# v3.net
KiCad netlist of a schematic drawn in Altium Designer
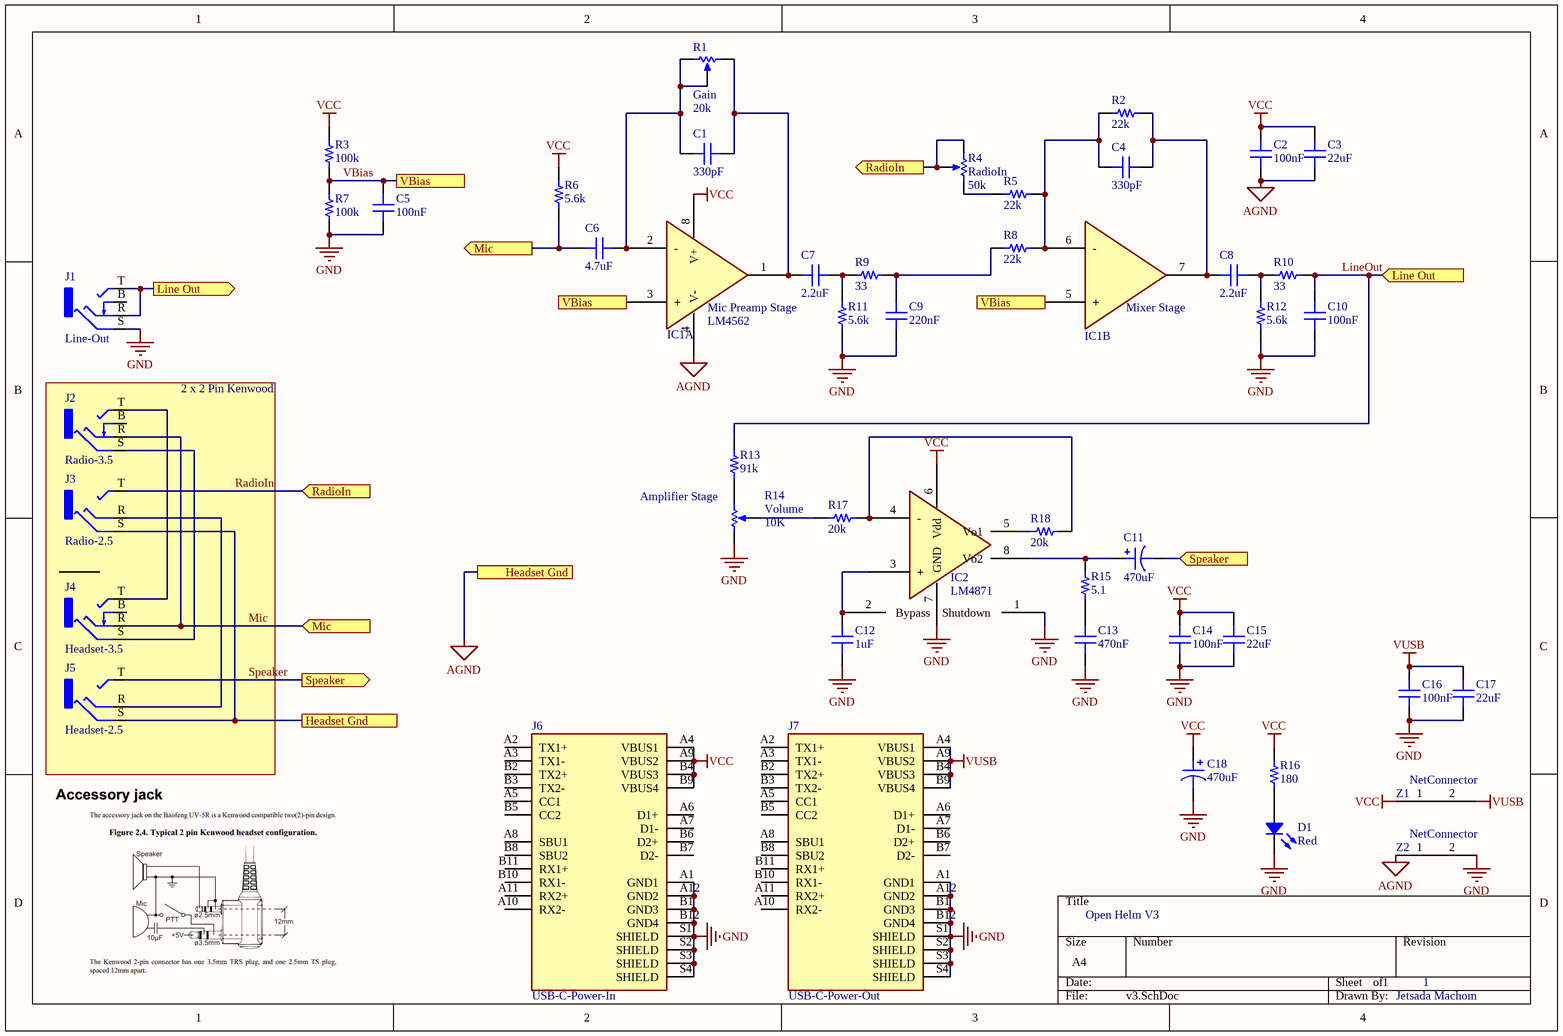
[diagram p0: v3.SchDoc]

(export (version "E")
  (design (tool "Eeschema 10.0.6"))
  (components
    (comp (ref "C1")
      (value "330pF")
      (footprint "CAP 0805_2012")
      (description "Multilayer Ceramic Capacitors MLCC - SMD/SMT 330pF 50V 0805 RoHS")
      (libsource (lib "Celestial Altium Library - altium_library") (part "Capacitor"))
    )
    (comp (ref "C2")
      (value "100nF")
      (footprint "CAP 0805_2012")
      (description "Multilayer Ceramic Capacitors MLCC - SMD/SMT 100nF 50V 0805 RoHS")
      (libsource (lib "Celestial Altium Library - altium_library") (part "Capacitor"))
    )
    (comp (ref "C3")
      (value "22uF")
      (footprint "CAP 0805_2012")
      (description "Multilayer Ceramic Capacitors MLCC - SMD/SMT 22uF 25V 0805 RoHS")
      (libsource (lib "Celestial Altium Library - altium_library") (part "Capacitor"))
    )
    (comp (ref "C4")
      (value "330pF")
      (footprint "CAP 0805_2012")
      (description "Multilayer Ceramic Capacitors MLCC - SMD/SMT 330pF 50V 0805 RoHS")
      (libsource (lib "Celestial Altium Library - altium_library") (part "Capacitor"))
    )
    (comp (ref "C5")
      (value "100nF")
      (footprint "CAP 0805_2012")
      (description "Multilayer Ceramic Capacitors MLCC - SMD/SMT 100nF 50V 0805 RoHS")
      (libsource (lib "Celestial Altium Library - altium_library") (part "Capacitor"))
    )
    (comp (ref "C6")
      (value "4.7uF")
      (footprint "CAP 0805_2012")
      (description "Multilayer Ceramic Capacitors MLCC - SMD/SMT 4.7uF 25V 0805 RoHS")
      (libsource (lib "Celestial Altium Library - altium_library") (part "Capacitor"))
    )
    (comp (ref "C7")
      (value "2.2uF")
      (footprint "CAP 0805_2012")
      (description "Multilayer Ceramic Capacitors MLCC - SMD/SMT 2.2uF 50V 0805 RoHS")
      (libsource (lib "Celestial Altium Library - altium_library") (part "Capacitor"))
    )
    (comp (ref "C8")
      (value "2.2uF")
      (footprint "CAP 0805_2012")
      (description "Multilayer Ceramic Capacitors MLCC - SMD/SMT 2.2uF 50V 0805 RoHS")
      (libsource (lib "Celestial Altium Library - altium_library") (part "Capacitor"))
    )
    (comp (ref "C9")
      (value "220nF")
      (footprint "CAP 0805_2012")
      (description "Multilayer Ceramic Capacitors MLCC - SMD/SMT 220nF 50V 0805 RoHS")
      (libsource (lib "Celestial Altium Library - altium_library") (part "Capacitor"))
    )
    (comp (ref "C10")
      (value "100nF")
      (footprint "CAP 0805_2012")
      (description "Multilayer Ceramic Capacitors MLCC - SMD/SMT 100nF 50V 0805 RoHS")
      (libsource (lib "Celestial Altium Library - altium_library") (part "Capacitor"))
    )
    (comp (ref "C11")
      (value "470uF")
      (footprint "EEEFT-D8")
      (description "SMD Aluminium Electrolytic Capacitor, Radial Can - SMD, 470 µF, 6.3 V, 0.16 ohm, FT Series")
      (libsource (lib "Celestial Altium Library - altium_library") (part "Polarised Capacitor"))
    )
    (comp (ref "C12")
      (value "1uF")
      (footprint "CAP 0805_2012")
      (description "Multilayer Ceramic Capacitors MLCC - SMD/SMT 100nF 50V 0805 RoHS")
      (libsource (lib "Celestial Altium Library - altium_library") (part "Capacitor"))
    )
    (comp (ref "C13")
      (value "470nF")
      (footprint "CAP 0805_2012")
      (description "Multilayer Ceramic Capacitors MLCC - SMD/SMT 470nF 50V 0805 RoHS")
      (libsource (lib "Celestial Altium Library - altium_library") (part "Capacitor"))
    )
    (comp (ref "C14")
      (value "100nF")
      (footprint "CAP 0805_2012")
      (description "Multilayer Ceramic Capacitors MLCC - SMD/SMT 100nF 50V 0805 RoHS")
      (libsource (lib "Celestial Altium Library - altium_library") (part "Capacitor"))
    )
    (comp (ref "C15")
      (value "22uF")
      (footprint "CAP 0805_2012")
      (description "Multilayer Ceramic Capacitors MLCC - SMD/SMT 22uF 25V 0805 RoHS")
      (libsource (lib "Celestial Altium Library - altium_library") (part "Capacitor"))
    )
    (comp (ref "C16")
      (value "100nF")
      (footprint "CAP 0805_2012")
      (description "Multilayer Ceramic Capacitors MLCC - SMD/SMT 100nF 50V 0805 RoHS")
      (libsource (lib "Celestial Altium Library - altium_library") (part "Capacitor"))
    )
    (comp (ref "C17")
      (value "22uF")
      (footprint "CAP 0805_2012")
      (description "Multilayer Ceramic Capacitors MLCC - SMD/SMT 22uF 25V 0805 RoHS")
      (libsource (lib "Celestial Altium Library - altium_library") (part "Capacitor"))
    )
    (comp (ref "C18")
      (value "470uF")
      (footprint "EEEFT-D8")
      (description "SMD Aluminium Electrolytic Capacitor, Radial Can - SMD, 470 µF, 10 V, 0.16 ohm, FT Series")
      (libsource (lib "") (part "Polarised Capacitor_1"))
    )
    (comp (ref "D1")
      (value "Red")
      (footprint "LED 0805_2012 RED")
      (description "LIGHT EMITTING DIODES (LED) RED 615~630NM 67~195MCD@20MA TOP VIEW 0805 ROHS")
      (libsource (lib "Celestial Altium Library - altium_library") (part "LED"))
    )
    (comp (ref "IC1")
      (value "LM4562")
      (footprint "LM4562")
      (description "Audio Power Amplifier, 2 Channel, ± 2.5V to ± 17V, SOIC, 8 Pins")
      (libsource (lib "ZLib") (part "LM4562"))
    )
    (comp (ref "IC2")
      (value "LM4871")
      (footprint "LM4871")
      (description "Audio Power Amplifier, 3 W, AB, 1 Channel, 2V to 5.5V, SOIC, 8 Pins")
      (libsource (lib "ZLib") (part "LM4871"))
    )
    (comp (ref "J1")
      (value "Line-Out")
      (footprint "KLBR4")
      (description "Phone Audio Connector, 3 Contacts, Socket, 3.5 mm, PCB Mount, Silver Plated Contacts, Metal Body")
      (libsource (lib "KLBR4") (part "KLBR4"))
    )
    (comp (ref "J2")
      (value "Radio-3.5")
      (footprint "KLBR4")
      (description "Phone Audio Connector, 3 Contacts, Socket, 3.5 mm, PCB Mount, Silver Plated Contacts, Metal Body")
      (libsource (lib "KLBR4") (part "KLBR4"))
    )
    (comp (ref "J3")
      (value "Radio-2.5")
      (footprint "LUMBERG150105")
      (description "Phone Audio Connector, 3 Contacts, Socket, 2.5 mm, PCB Mount, Silver Plated Contacts, Metal Body")
      (libsource (lib "ZLib") (part "LUMBERG150105"))
    )
    (comp (ref "J4")
      (value "Headset-3.5")
      (footprint "KLBR4")
      (description "Phone Audio Connector, 3 Contacts, Socket, 3.5 mm, PCB Mount, Silver Plated Contacts, Metal Body")
      (libsource (lib "KLBR4") (part "KLBR4"))
    )
    (comp (ref "J5")
      (value "Headset-2.5")
      (footprint "LUMBERG150105")
      (description "Phone Audio Connector, 3 Contacts, Socket, 2.5 mm, PCB Mount, Silver Plated Contacts, Metal Body")
      (libsource (lib "ZLib") (part "LUMBERG150105"))
    )
    (comp (ref "J6")
      (value "USB-C-Power-In")
      (footprint "MC001002")
      (description "USB Connector, USB Type C, USB 3.1, Receptacle, 24 Ways, Surface Mount, Through Hole Mount")
      (libsource (lib "ZLib") (part "USBC"))
    )
    (comp (ref "J7")
      (value "USB-C-Power-Out")
      (footprint "MC001002")
      (description "USB Connector, USB Type C, USB 3.1, Receptacle, 24 Ways, Surface Mount, Through Hole Mount")
      (libsource (lib "ZLib") (part "USBC"))
    )
    (comp (ref "R1")
      (value "Gain")
      (footprint "3224W")
      (description "20K ±10% ±100ppm/°C Variable Resistors")
      (fields (field (name "ALTIUM_VALUE") "20k"))
      (libsource (lib "ZLib") (part "RPot"))
    )
    (comp (ref "R2")
      (value "22k")
      (footprint "RES 0805_2012")
      (description "Chip Resistor - Surface Mount 22KOhms ±1% 1/8W 0805 RoHS")
      (libsource (lib "Celestial Altium Library - altium_library") (part "Resistor"))
    )
    (comp (ref "R3")
      (value "100k")
      (footprint "RES 0805_2012")
      (description "Chip Resistor - Surface Mount 100KOhms ±1% 1/8W 0805 RoHS")
      (libsource (lib "Celestial Altium Library - altium_library") (part "Resistor"))
    )
    (comp (ref "R4")
      (value "RadioIn")
      (footprint "3224W")
      (description "50K ±10% ±100ppm/°C Variable Resistors")
      (fields (field (name "ALTIUM_VALUE") "50k"))
      (libsource (lib "ZLib") (part "RPot"))
    )
    (comp (ref "R5")
      (value "22k")
      (footprint "RES 0805_2012")
      (description "Chip Resistor - Surface Mount 22KOhms ±1% 1/8W 0805 RoHS")
      (libsource (lib "Celestial Altium Library - altium_library") (part "Resistor"))
    )
    (comp (ref "R6")
      (value "5.6k")
      (footprint "RES 0805_2012")
      (description "Chip Resistor - Surface Mount 5.6KOhms ±1% 1/8W 0805 RoHS")
      (libsource (lib "Celestial Altium Library - altium_library") (part "Resistor"))
    )
    (comp (ref "R7")
      (value "100k")
      (footprint "RES 0805_2012")
      (description "Chip Resistor - Surface Mount 100KOhms ±1% 1/8W 0805 RoHS")
      (libsource (lib "Celestial Altium Library - altium_library") (part "Resistor"))
    )
    (comp (ref "R8")
      (value "22k")
      (footprint "RES 0805_2012")
      (description "Chip Resistor - Surface Mount 22KOhms ±1% 1/8W 0805 RoHS")
      (libsource (lib "Celestial Altium Library - altium_library") (part "Resistor"))
    )
    (comp (ref "R9")
      (value "33")
      (footprint "RES 0805_2012")
      (description "Chip Resistor - Surface Mount 33Ohms ±1% 1/8W 0805 RoHS")
      (libsource (lib "Celestial Altium Library - altium_library") (part "Resistor"))
    )
    (comp (ref "R10")
      (value "33")
      (footprint "RES 0805_2012")
      (description "Chip Resistor - Surface Mount 33Ohms ±1% 1/8W 0805 RoHS")
      (libsource (lib "Celestial Altium Library - altium_library") (part "Resistor"))
    )
    (comp (ref "R11")
      (value "5.6k")
      (footprint "RES 0805_2012")
      (description "Chip Resistor - Surface Mount 5.6KOhms ±1% 1/8W 0805 RoHS")
      (libsource (lib "Celestial Altium Library - altium_library") (part "Resistor"))
    )
    (comp (ref "R12")
      (value "5.6k")
      (footprint "RES 0805_2012")
      (description "Chip Resistor - Surface Mount 5.6KOhms ±1% 1/8W 0805 RoHS")
      (libsource (lib "Celestial Altium Library - altium_library") (part "Resistor"))
    )
    (comp (ref "R13")
      (value "91k")
      (footprint "RES 0805_2012")
      (description "Chip Resistor - Surface Mount 91KOhms ±1% 1/8W 0805 RoHS")
      (libsource (lib "Celestial Altium Library - altium_library") (part "Resistor"))
    )
    (comp (ref "R14")
      (value "Volume")
      (footprint "RK09")
      (description "Rotary Potentiometer, 10 kohm, 1 Turns, Logarithmic, 50 mW, ± 20%, RK09 Series")
      (fields (field (name "ALTIUM_VALUE") "10K"))
      (libsource (lib "ZLib") (part "RPot"))
    )
    (comp (ref "R15")
      (value "5.1")
      (footprint "RES 0805_2012")
      (description "Chip Resistor - Surface Mount 5.1Ohms ±1% 1/8W 0805 RoHS")
      (libsource (lib "Celestial Altium Library - altium_library") (part "Resistor"))
    )
    (comp (ref "R16")
      (value "180")
      (footprint "RES 0805_2012")
      (description "Chip Resistor - Surface Mount 180Ohms ±1% 1/8W 0805 RoHS")
      (libsource (lib "Celestial Altium Library - altium_library") (part "Resistor"))
    )
    (comp (ref "R17")
      (value "20k")
      (footprint "RES 0805_2012")
      (description "Chip Resistor - Surface Mount 20KOhms ±1% 1/8W 0805 RoHS")
      (libsource (lib "Celestial Altium Library - altium_library") (part "Resistor"))
    )
    (comp (ref "R18")
      (value "20k")
      (footprint "RES 0805_2012")
      (description "Chip Resistor - Surface Mount 20KOhms ±1% 1/8W 0805 RoHS")
      (libsource (lib "Celestial Altium Library - altium_library") (part "Resistor"))
    )
    (comp (ref "Z1")
      (value "NetConnector")
      (footprint "NetConnector")
      (libsource (lib "ZLib") (part "NetConnector"))
    )
    (comp (ref "Z2")
      (value "NetConnector")
      (footprint "NetConnector")
      (libsource (lib "ZLib") (part "NetConnector"))
    )
  )
  (nets
    (net (code "1") (name "/LineOut") (class "Default")
      (node (ref "C10") (pin "2") (pinfunction "2_2") (pintype "passive"))
      (node (ref "J1") (pin "R") (pinfunction "R_R") (pintype "passive"))
      (node (ref "J1") (pin "T") (pinfunction "T_T") (pintype "passive"))
      (node (ref "R10") (pin "1") (pinfunction "1_1") (pintype "passive"))
      (node (ref "R13") (pin "1") (pinfunction "1_1") (pintype "passive"))
    )
    (net (code "2") (name "/Mic") (class "Default")
      (node (ref "C6") (pin "1") (pinfunction "1_1") (pintype "passive"))
      (node (ref "J2") (pin "R") (pinfunction "R_R") (pintype "passive"))
      (node (ref "J4") (pin "R") (pinfunction "R_R") (pintype "passive"))
      (node (ref "R6") (pin "1") (pinfunction "1_1") (pintype "passive"))
    )
    (net (code "3") (name "/RadioIn") (class "Default")
      (node (ref "J3") (pin "T") (pinfunction "T_T") (pintype "passive"))
      (node (ref "R4") (pin "1") (pinfunction "TOP_1") (pintype "passive"))
      (node (ref "R4") (pin "2") (pinfunction "TAP_2") (pintype "passive"))
    )
    (net (code "4") (name "/Speaker") (class "Default")
      (node (ref "C11") (pin "2") (pinfunction "2_2") (pintype "passive"))
      (node (ref "J5") (pin "T") (pinfunction "T_T") (pintype "passive"))
    )
    (net (code "5") (name "/VBias") (class "Default")
      (node (ref "C5") (pin "2") (pinfunction "2_2") (pintype "passive"))
      (node (ref "IC1") (pin "3") (pinfunction "+_3") (pintype "passive"))
      (node (ref "IC1") (pin "5") (pinfunction "+_5") (pintype "passive"))
      (node (ref "R3") (pin "1") (pinfunction "1_1") (pintype "passive"))
      (node (ref "R7") (pin "2") (pinfunction "2_2") (pintype "passive"))
    )
    (net (code "6") (name "AGND") (class "Default")
      (node (ref "C2") (pin "1") (pinfunction "1_1") (pintype "passive"))
      (node (ref "C3") (pin "1") (pinfunction "1_1") (pintype "passive"))
      (node (ref "IC1") (pin "4") (pinfunction "V-_4") (pintype "power_in"))
      (node (ref "J3") (pin "S") (pinfunction "S_S") (pintype "passive"))
      (node (ref "J5") (pin "S") (pinfunction "S_S") (pintype "passive"))
      (node (ref "Z2") (pin "1") (pinfunction "1_1") (pintype "passive"))
    )
    (net (code "7") (name "GND") (class "Default")
      (node (ref "C10") (pin "1") (pinfunction "1_1") (pintype "passive"))
      (node (ref "C12") (pin "1") (pinfunction "1_1") (pintype "passive"))
      (node (ref "C13") (pin "1") (pinfunction "1_1") (pintype "passive"))
      (node (ref "C14") (pin "1") (pinfunction "1_1") (pintype "passive"))
      (node (ref "C15") (pin "1") (pinfunction "1_1") (pintype "passive"))
      (node (ref "C16") (pin "1") (pinfunction "1_1") (pintype "passive"))
      (node (ref "C17") (pin "1") (pinfunction "1_1") (pintype "passive"))
      (node (ref "C18") (pin "2") (pinfunction "2_2") (pintype "passive"))
      (node (ref "C5") (pin "1") (pinfunction "1_1") (pintype "passive"))
      (node (ref "C9") (pin "1") (pinfunction "1_1") (pintype "passive"))
      (node (ref "D1") (pin "2") (pinfunction "2_2") (pintype "passive"))
      (node (ref "IC2") (pin "1") (pinfunction "Shutdown_1") (pintype "passive"))
      (node (ref "IC2") (pin "7") (pinfunction "GND_7") (pintype "power_in"))
      (node (ref "J1") (pin "S") (pinfunction "S_S") (pintype "passive"))
      (node (ref "J6") (pin "A1") (pinfunction "GND1_A1") (pintype "passive"))
      (node (ref "J6") (pin "A12") (pinfunction "GND2_A12") (pintype "passive"))
      (node (ref "J6") (pin "B1") (pinfunction "GND3_B1") (pintype "passive"))
      (node (ref "J6") (pin "B12") (pinfunction "GND4_B12") (pintype "passive"))
      (node (ref "J6") (pin "S1") (pinfunction "SHIELD_S1") (pintype "passive"))
      (node (ref "J6") (pin "S2") (pinfunction "SHIELD_S2") (pintype "passive"))
      (node (ref "J6") (pin "S3") (pinfunction "SHIELD_S3") (pintype "passive"))
      (node (ref "J6") (pin "S4") (pinfunction "SHIELD_S4") (pintype "passive"))
      (node (ref "J7") (pin "A1") (pinfunction "GND1_A1") (pintype "passive"))
      (node (ref "J7") (pin "A12") (pinfunction "GND2_A12") (pintype "passive"))
      (node (ref "J7") (pin "B1") (pinfunction "GND3_B1") (pintype "passive"))
      (node (ref "J7") (pin "B12") (pinfunction "GND4_B12") (pintype "passive"))
      (node (ref "J7") (pin "S1") (pinfunction "SHIELD_S1") (pintype "passive"))
      (node (ref "J7") (pin "S2") (pinfunction "SHIELD_S2") (pintype "passive"))
      (node (ref "J7") (pin "S3") (pinfunction "SHIELD_S3") (pintype "passive"))
      (node (ref "J7") (pin "S4") (pinfunction "SHIELD_S4") (pintype "passive"))
      (node (ref "R11") (pin "1") (pinfunction "1_1") (pintype "passive"))
      (node (ref "R12") (pin "1") (pinfunction "1_1") (pintype "passive"))
      (node (ref "R14") (pin "1") (pinfunction "TOP_1") (pintype "passive"))
      (node (ref "R7") (pin "1") (pinfunction "1_1") (pintype "passive"))
      (node (ref "Z2") (pin "2") (pinfunction "2_2") (pintype "passive"))
    )
    (net (code "8") (name "Net-(C7-Pad2)") (class "Default")
      (node (ref "C7") (pin "2") (pinfunction "2_2") (pintype "passive"))
      (node (ref "R11") (pin "2") (pinfunction "2_2") (pintype "passive"))
      (node (ref "R9") (pin "2") (pinfunction "2_2") (pintype "passive"))
    )
    (net (code "9") (name "Net-(C8-Pad2)") (class "Default")
      (node (ref "C8") (pin "2") (pinfunction "2_2") (pintype "passive"))
      (node (ref "R10") (pin "2") (pinfunction "2_2") (pintype "passive"))
      (node (ref "R12") (pin "2") (pinfunction "2_2") (pintype "passive"))
    )
    (net (code "10") (name "Net-(C9-Pad2)") (class "Default")
      (node (ref "C9") (pin "2") (pinfunction "2_2") (pintype "passive"))
      (node (ref "R8") (pin "2") (pinfunction "2_2") (pintype "passive"))
      (node (ref "R9") (pin "1") (pinfunction "1_1") (pintype "passive"))
    )
    (net (code "11") (name "Net-(C13-Pad2)") (class "Default")
      (node (ref "C13") (pin "2") (pinfunction "2_2") (pintype "passive"))
      (node (ref "R15") (pin "2") (pinfunction "2_2") (pintype "passive"))
    )
    (net (code "12") (name "Net-(D1-Pad1)") (class "Default")
      (node (ref "D1") (pin "1") (pinfunction "1_1") (pintype "passive"))
      (node (ref "R16") (pin "1") (pinfunction "1_1") (pintype "passive"))
    )
    (net (code "13") (name "Net-(IC1A--)") (class "Default")
      (node (ref "C1") (pin "1") (pinfunction "1_1") (pintype "passive"))
      (node (ref "C6") (pin "2") (pinfunction "2_2") (pintype "passive"))
      (node (ref "IC1") (pin "2") (pinfunction "-_2") (pintype "passive"))
      (node (ref "R1") (pin "1") (pinfunction "TOP_1") (pintype "passive"))
      (node (ref "R1") (pin "2") (pinfunction "TAP_2") (pintype "passive"))
    )
    (net (code "14") (name "Net-(IC1A-OUT)") (class "Default")
      (node (ref "C1") (pin "2") (pinfunction "2_2") (pintype "passive"))
      (node (ref "C7") (pin "1") (pinfunction "1_1") (pintype "passive"))
      (node (ref "IC1") (pin "1") (pinfunction "OUT_1") (pintype "passive"))
      (node (ref "R1") (pin "3") (pinfunction "BOT_3") (pintype "passive"))
    )
    (net (code "15") (name "Net-(IC1B--)") (class "Default")
      (node (ref "C4") (pin "1") (pinfunction "1_1") (pintype "passive"))
      (node (ref "IC1") (pin "6") (pinfunction "-_6") (pintype "passive"))
      (node (ref "R2") (pin "2") (pinfunction "2_2") (pintype "passive"))
      (node (ref "R5") (pin "1") (pinfunction "1_1") (pintype "passive"))
      (node (ref "R8") (pin "1") (pinfunction "1_1") (pintype "passive"))
    )
    (net (code "16") (name "Net-(IC1B-OUT)") (class "Default")
      (node (ref "C4") (pin "2") (pinfunction "2_2") (pintype "passive"))
      (node (ref "C8") (pin "1") (pinfunction "1_1") (pintype "passive"))
      (node (ref "IC1") (pin "7") (pinfunction "OUT_7") (pintype "passive"))
      (node (ref "R2") (pin "1") (pinfunction "1_1") (pintype "passive"))
    )
    (net (code "17") (name "Net-(IC2-+)") (class "Default")
      (node (ref "C12") (pin "2") (pinfunction "2_2") (pintype "passive"))
      (node (ref "IC2") (pin "2") (pinfunction "Bypass_2") (pintype "passive"))
      (node (ref "IC2") (pin "3") (pinfunction "+_3") (pintype "passive"))
    )
    (net (code "18") (name "Net-(IC2--)") (class "Default")
      (node (ref "IC2") (pin "4") (pinfunction "-_4") (pintype "passive"))
      (node (ref "R17") (pin "2") (pinfunction "2_2") (pintype "passive"))
      (node (ref "R18") (pin "2") (pinfunction "2_2") (pintype "passive"))
    )
    (net (code "19") (name "Net-(IC2-Vo1)") (class "Default")
      (node (ref "IC2") (pin "5") (pinfunction "Vo1_5") (pintype "passive"))
      (node (ref "R18") (pin "1") (pinfunction "1_1") (pintype "passive"))
    )
    (net (code "20") (name "Net-(IC2-Vo2)") (class "Default")
      (node (ref "C11") (pin "1") (pinfunction "1_1") (pintype "passive"))
      (node (ref "IC2") (pin "8") (pinfunction "Vo2_8") (pintype "passive"))
      (node (ref "R15") (pin "1") (pinfunction "1_1") (pintype "passive"))
    )
    (net (code "21") (name "Net-(J2-PadS)") (class "Default")
      (node (ref "J2") (pin "S") (pinfunction "S_S") (pintype "passive"))
      (node (ref "J4") (pin "S") (pinfunction "S_S") (pintype "passive"))
    )
    (net (code "22") (name "Net-(J2-PadT)") (class "Default")
      (node (ref "J2") (pin "T") (pinfunction "T_T") (pintype "passive"))
      (node (ref "J4") (pin "T") (pinfunction "T_T") (pintype "passive"))
    )
    (net (code "23") (name "Net-(J3-PadR)") (class "Default")
      (node (ref "J3") (pin "R") (pinfunction "R_R") (pintype "passive"))
      (node (ref "J5") (pin "R") (pinfunction "R_R") (pintype "passive"))
    )
    (net (code "24") (name "Net-(R4-BOT)") (class "Default")
      (node (ref "R4") (pin "3") (pinfunction "BOT_3") (pintype "passive"))
      (node (ref "R5") (pin "2") (pinfunction "2_2") (pintype "passive"))
    )
    (net (code "25") (name "Net-(R14-BOT)") (class "Default")
      (node (ref "R13") (pin "2") (pinfunction "2_2") (pintype "passive"))
      (node (ref "R14") (pin "3") (pinfunction "BOT_3") (pintype "passive"))
    )
    (net (code "26") (name "Net-(R14-TAP)") (class "Default")
      (node (ref "R14") (pin "2") (pinfunction "TAP_2") (pintype "passive"))
      (node (ref "R17") (pin "1") (pinfunction "1_1") (pintype "passive"))
    )
    (net (code "27") (name "VCC") (class "Default")
      (node (ref "C14") (pin "2") (pinfunction "2_2") (pintype "passive"))
      (node (ref "C15") (pin "2") (pinfunction "2_2") (pintype "passive"))
      (node (ref "C18") (pin "1") (pinfunction "1_1") (pintype "passive"))
      (node (ref "C2") (pin "2") (pinfunction "2_2") (pintype "passive"))
      (node (ref "C3") (pin "2") (pinfunction "2_2") (pintype "passive"))
      (node (ref "IC1") (pin "8") (pinfunction "V+_8") (pintype "power_in"))
      (node (ref "IC2") (pin "6") (pinfunction "Vdd_6") (pintype "power_in"))
      (node (ref "J6") (pin "A4") (pinfunction "VBUS1_A4") (pintype "passive"))
      (node (ref "J6") (pin "A9") (pinfunction "VBUS2_A9") (pintype "passive"))
      (node (ref "J6") (pin "B4") (pinfunction "VBUS3_B4") (pintype "passive"))
      (node (ref "J6") (pin "B9") (pinfunction "VBUS4_B9") (pintype "passive"))
      (node (ref "R16") (pin "2") (pinfunction "2_2") (pintype "passive"))
      (node (ref "R3") (pin "2") (pinfunction "2_2") (pintype "passive"))
      (node (ref "R6") (pin "2") (pinfunction "2_2") (pintype "passive"))
      (node (ref "Z1") (pin "1") (pinfunction "1_1") (pintype "passive"))
    )
    (net (code "28") (name "VUSB") (class "Default")
      (node (ref "C16") (pin "2") (pinfunction "2_2") (pintype "passive"))
      (node (ref "C17") (pin "2") (pinfunction "2_2") (pintype "passive"))
      (node (ref "J7") (pin "A4") (pinfunction "VBUS1_A4") (pintype "passive"))
      (node (ref "J7") (pin "A9") (pinfunction "VBUS2_A9") (pintype "passive"))
      (node (ref "J7") (pin "B4") (pinfunction "VBUS3_B4") (pintype "passive"))
      (node (ref "J7") (pin "B9") (pinfunction "VBUS4_B9") (pintype "passive"))
      (node (ref "Z1") (pin "2") (pinfunction "2_2") (pintype "passive"))
    )
    (net (code "29") (name "unconnected-(J1-PadB)") (class "Default")
      (node (ref "J1") (pin "B") (pinfunction "B_B") (pintype "passive"))
    )
    (net (code "30") (name "unconnected-(J2-PadB)") (class "Default")
      (node (ref "J2") (pin "B") (pinfunction "B_B") (pintype "passive"))
    )
    (net (code "31") (name "unconnected-(J4-PadB)") (class "Default")
      (node (ref "J4") (pin "B") (pinfunction "B_B") (pintype "passive"))
    )
    (net (code "32") (name "unconnected-(J6-CC1-PadA5)") (class "Default")
      (node (ref "J6") (pin "A5") (pinfunction "CC1_A5") (pintype "passive"))
    )
    (net (code "33") (name "unconnected-(J6-CC2-PadB5)") (class "Default")
      (node (ref "J6") (pin "B5") (pinfunction "CC2_B5") (pintype "passive"))
    )
    (net (code "34") (name "unconnected-(J6-D1+-PadA6)") (class "Default")
      (node (ref "J6") (pin "A6") (pinfunction "D1+_A6") (pintype "passive"))
    )
    (net (code "35") (name "unconnected-(J6-D1--PadA7)") (class "Default")
      (node (ref "J6") (pin "A7") (pinfunction "D1-_A7") (pintype "passive"))
    )
    (net (code "36") (name "unconnected-(J6-D2+-PadB6)") (class "Default")
      (node (ref "J6") (pin "B6") (pinfunction "D2+_B6") (pintype "passive"))
    )
    (net (code "37") (name "unconnected-(J6-D2--PadB7)") (class "Default")
      (node (ref "J6") (pin "B7") (pinfunction "D2-_B7") (pintype "passive"))
    )
    (net (code "38") (name "unconnected-(J6-RX1+-PadB11)") (class "Default")
      (node (ref "J6") (pin "B11") (pinfunction "RX1+_B11") (pintype "passive"))
    )
    (net (code "39") (name "unconnected-(J6-RX1--PadB10)") (class "Default")
      (node (ref "J6") (pin "B10") (pinfunction "RX1-_B10") (pintype "passive"))
    )
    (net (code "40") (name "unconnected-(J6-RX2+-PadA11)") (class "Default")
      (node (ref "J6") (pin "A11") (pinfunction "RX2+_A11") (pintype "passive"))
    )
    (net (code "41") (name "unconnected-(J6-RX2--PadA10)") (class "Default")
      (node (ref "J6") (pin "A10") (pinfunction "RX2-_A10") (pintype "passive"))
    )
    (net (code "42") (name "unconnected-(J6-SBU1-PadA8)") (class "Default")
      (node (ref "J6") (pin "A8") (pinfunction "SBU1_A8") (pintype "passive"))
    )
    (net (code "43") (name "unconnected-(J6-SBU2-PadB8)") (class "Default")
      (node (ref "J6") (pin "B8") (pinfunction "SBU2_B8") (pintype "passive"))
    )
    (net (code "44") (name "unconnected-(J6-TX1+-PadA2)") (class "Default")
      (node (ref "J6") (pin "A2") (pinfunction "TX1+_A2") (pintype "passive"))
    )
    (net (code "45") (name "unconnected-(J6-TX1--PadA3)") (class "Default")
      (node (ref "J6") (pin "A3") (pinfunction "TX1-_A3") (pintype "passive"))
    )
    (net (code "46") (name "unconnected-(J6-TX2+-PadB2)") (class "Default")
      (node (ref "J6") (pin "B2") (pinfunction "TX2+_B2") (pintype "passive"))
    )
    (net (code "47") (name "unconnected-(J6-TX2--PadB3)") (class "Default")
      (node (ref "J6") (pin "B3") (pinfunction "TX2-_B3") (pintype "passive"))
    )
    (net (code "48") (name "unconnected-(J7-CC1-PadA5)") (class "Default")
      (node (ref "J7") (pin "A5") (pinfunction "CC1_A5") (pintype "passive"))
    )
    (net (code "49") (name "unconnected-(J7-CC2-PadB5)") (class "Default")
      (node (ref "J7") (pin "B5") (pinfunction "CC2_B5") (pintype "passive"))
    )
    (net (code "50") (name "unconnected-(J7-D1+-PadA6)") (class "Default")
      (node (ref "J7") (pin "A6") (pinfunction "D1+_A6") (pintype "passive"))
    )
    (net (code "51") (name "unconnected-(J7-D1--PadA7)") (class "Default")
      (node (ref "J7") (pin "A7") (pinfunction "D1-_A7") (pintype "passive"))
    )
    (net (code "52") (name "unconnected-(J7-D2+-PadB6)") (class "Default")
      (node (ref "J7") (pin "B6") (pinfunction "D2+_B6") (pintype "passive"))
    )
    (net (code "53") (name "unconnected-(J7-D2--PadB7)") (class "Default")
      (node (ref "J7") (pin "B7") (pinfunction "D2-_B7") (pintype "passive"))
    )
    (net (code "54") (name "unconnected-(J7-RX1+-PadB11)") (class "Default")
      (node (ref "J7") (pin "B11") (pinfunction "RX1+_B11") (pintype "passive"))
    )
    (net (code "55") (name "unconnected-(J7-RX1--PadB10)") (class "Default")
      (node (ref "J7") (pin "B10") (pinfunction "RX1-_B10") (pintype "passive"))
    )
    (net (code "56") (name "unconnected-(J7-RX2+-PadA11)") (class "Default")
      (node (ref "J7") (pin "A11") (pinfunction "RX2+_A11") (pintype "passive"))
    )
    (net (code "57") (name "unconnected-(J7-RX2--PadA10)") (class "Default")
      (node (ref "J7") (pin "A10") (pinfunction "RX2-_A10") (pintype "passive"))
    )
    (net (code "58") (name "unconnected-(J7-SBU1-PadA8)") (class "Default")
      (node (ref "J7") (pin "A8") (pinfunction "SBU1_A8") (pintype "passive"))
    )
    (net (code "59") (name "unconnected-(J7-SBU2-PadB8)") (class "Default")
      (node (ref "J7") (pin "B8") (pinfunction "SBU2_B8") (pintype "passive"))
    )
    (net (code "60") (name "unconnected-(J7-TX1+-PadA2)") (class "Default")
      (node (ref "J7") (pin "A2") (pinfunction "TX1+_A2") (pintype "passive"))
    )
    (net (code "61") (name "unconnected-(J7-TX1--PadA3)") (class "Default")
      (node (ref "J7") (pin "A3") (pinfunction "TX1-_A3") (pintype "passive"))
    )
    (net (code "62") (name "unconnected-(J7-TX2+-PadB2)") (class "Default")
      (node (ref "J7") (pin "B2") (pinfunction "TX2+_B2") (pintype "passive"))
    )
    (net (code "63") (name "unconnected-(J7-TX2--PadB3)") (class "Default")
      (node (ref "J7") (pin "B3") (pinfunction "TX2-_B3") (pintype "passive"))
    )
  )
)
